# Input_Protection.net
KiCad netlist of a schematic drawn in Altium Designer
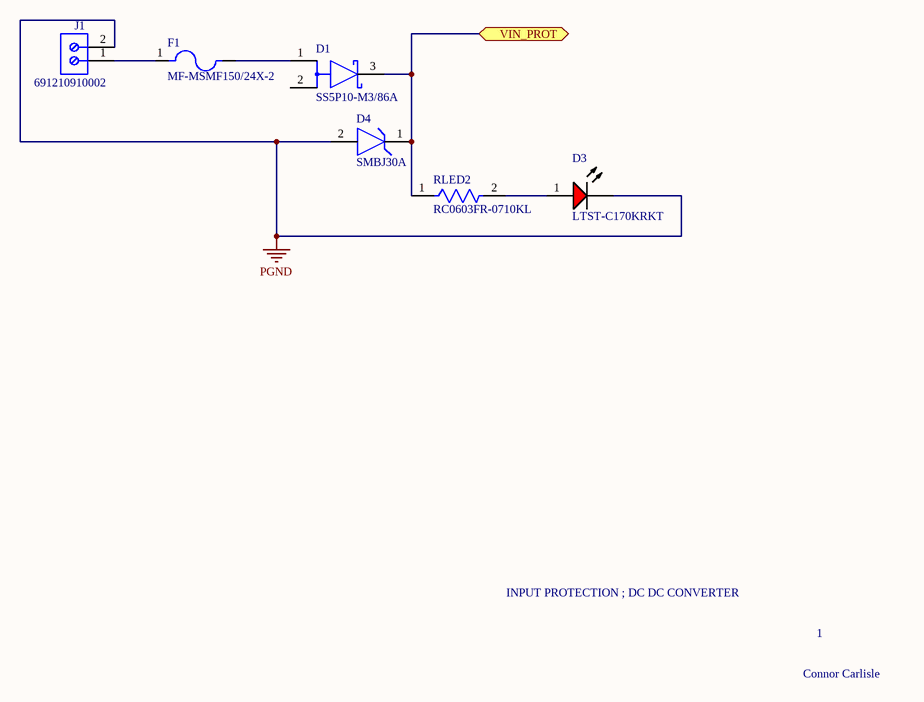
[diagram p0: Input_Protection.SchDoc]

(export (version "E")
  (design (tool "Eeschema 10.0.6"))
  (components
    (comp (ref "D1")
      (value "SS5P10-M3/86A")
      (footprint "FP-95570-MFG")
      (description "DIODE SCHOTTKY 100V 5A TO277A")
      (libsource (lib "Altium Content Vault") (part "03725f8997c85b601c823eea96032f8"))
    )
    (comp (ref "D3")
      (value "LTST-C170KRKT")
      (footprint "LTST-C170KRKT_V")
      (description "LED Red, 75 mW, 54 mcd, -55 to 85 degC, 2-Pin SMD, RoHS, Tape and Reel")
      (fields (field (name "MANUFACTURER") "Lite-On"))
      (libsource (lib "Altium Content Vault") (part "LED-RED-AK-2"))
    )
    (comp (ref "D4")
      (value "SMBJ30A")
      (footprint "FP-DO-214AA_SMB_J-Bend-MFG")
      (description "SMBJ30A SMBJ Series 48.4 V 0.6 kW Surface Mount Uni-Directional TVS Diode - DO-214AA")
      (fields (field (name "VOLTAGE") "30V"))
      (libsource (lib "Altium Content Vault") (part "673ecd2ea4d7fb87b4005b0cb348b7d"))
    )
    (comp (ref "F1")
      (value "MF-MSMF150/24X-2")
      (footprint "FUSER_MF-MSMF150/24X-2")
      (description "Polymeric PTC Resettable Fuse 24V 1.5 A Ih Surface Mount 1812 (4532 Metric), Concave")
      (fields (field (name "DIGI-KEY_PART_NUMBER") "MF-MSMF150/24X-2TR-ND") (field (name "MF") "Bourns"))
      (libsource (lib "Connor Carlisle") (part "MF-MSMF150/24X-2"))
    )
    (comp (ref "J1")
      (value "691210910002")
      (footprint "691210910002")
      (description "Tb, Wire To Brd, R/A, 2Way, 18Awg Rohs Compliant: Yes")
      (libsource (lib "Altium Content Vault") (part "TBL - 1R - 02P - Screw"))
    )
    (comp (ref "RLED2")
      (value "RC0603FR-0710KL")
      (footprint "FP-RC0603-0_55-IPC_C")
      (description "RES 10K OHM 1% 1/10W 0603")
      (fields (field (name "TOLERANCE") "1%"))
      (libsource (lib "Altium Content Vault") (part "1029c3af85768c4190bb7ad29bc67b5"))
    )
  )
  (nets
    (net (code "1") (name "/VIN_PROT") (class "Default")
      (node (ref "D1") (pin "3") (pinfunction "C_3") (pintype "passive"))
      (node (ref "D4") (pin "1") (pinfunction "C_1") (pintype "passive"))
      (node (ref "RLED2") (pin "1") (pinfunction "1_1") (pintype "passive"))
    )
    (net (code "2") (name "Net-(D1-A-Pad1)") (class "Default")
      (node (ref "D1") (pin "1") (pinfunction "A_1") (pintype "passive"))
      (node (ref "F1") (pin "2") (pinfunction "2_2") (pintype "passive"))
    )
    (net (code "3") (name "Net-(D3-A)") (class "Default")
      (node (ref "D3") (pin "1") (pinfunction "A_1") (pintype "passive"))
      (node (ref "RLED2") (pin "2") (pinfunction "2_2") (pintype "passive"))
    )
    (net (code "4") (name "Net-(F1-Pad1)") (class "Default")
      (node (ref "F1") (pin "1") (pinfunction "1_1") (pintype "passive"))
      (node (ref "J1") (pin "1") (pinfunction "1_1") (pintype "passive"))
    )
    (net (code "5") (name "PGND") (class "Default")
      (node (ref "D3") (pin "2") (pinfunction "K_2") (pintype "passive"))
      (node (ref "D4") (pin "2") (pinfunction "A_2") (pintype "passive"))
      (node (ref "J1") (pin "2") (pinfunction "2_2") (pintype "passive"))
    )
    (net (code "6") (name "unconnected-(D1-A-Pad2)") (class "Default")
      (node (ref "D1") (pin "2") (pinfunction "A_2") (pintype "passive"))
    )
  )
)
